# Display.net
KiCad netlist of a schematic drawn in Altium Designer
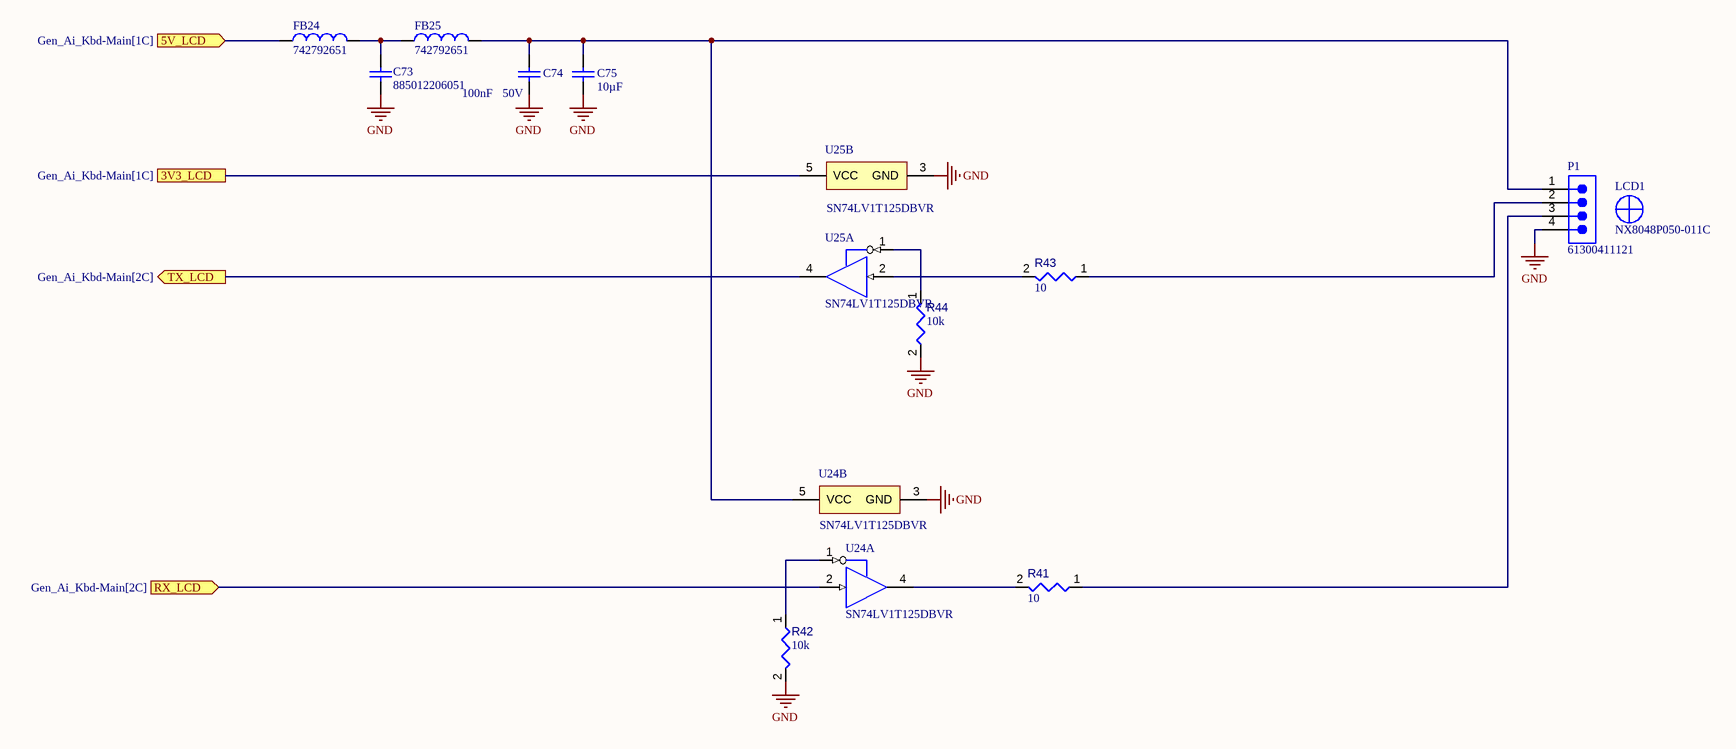
[diagram p0: Display.SchDoc]

(export (version "E")
  (design (tool "Eeschema 10.0.6"))
  (components
    (comp (ref "C73")
      (value "885012206051")
      (footprint "WCAP-CSGP_0603_L1.6W0.8H0.8_Reflow")
      (description "885012206051 Cap Cer 0.68UF 16V X7R 0603")
      (fields (field (name "TOLERANCE") "10%"))
      (libsource (lib "Altium Content Vault") (part "Capacitor_Non-Polarized"))
    )
    (comp (ref "C74")
      (value "885012206095")
      (footprint "WCAP-CSGP_0603_L1.6W0.8H0.8_Reflow")
      (description "WCAP-CSGP Multilayer Ceramic Chip Capacitor, General Purpose, size 0603, X7R, 100nF, 50VDC")
      (fields
        (field (name "CAPACITANCE") "100nF")
        (field (name "MANUFACTURER") "Wurth Elektronik")
        (field (name "RATED VOLTAGE (DC)") "50V")
      )
      (libsource (lib "Test365") (part "885012209047R"))
    )
    (comp (ref "C75")
      (value "885012106006")
      (footprint "WCAP-CSGP_0603_L1.6W0.8H0.8_Reflow")
      (description "WCAP-CSGP Multilayer Ceramic Chip Capacitor, General Purpose, size 0603, X5R, 10µF, 6.3VDC")
      (fields (field (name "MANUFACTURER") "Wurth Elektronik") (field (name "CAPACITANCE") "10µF"))
      (libsource (lib "Test365") (part "885012209047R"))
    )
    (comp (ref "FB24")
      (value "742792651")
      (footprint "WE-CBF_0603_L1.6W0.8H0.8_HC")
      (fields (field (name "TOLERANCE") "25%"))
      (libsource (lib "Altium Content Vault") (part "Ferrite"))
    )
    (comp (ref "FB25")
      (value "742792651")
      (footprint "WE-CBF_0603_L1.6W0.8H0.8_HC")
      (fields (field (name "TOLERANCE") "25%"))
      (libsource (lib "Altium Content Vault") (part "Ferrite"))
    )
    (comp (ref "LCD1")
      (value "NX8048P050-011C")
      (footprint "NEXTION 5.5Inch")
      (description "Nextion 5.5 Inch LCD")
      (libsource (lib "Test365") (part "NX8048P050-011C"))
    )
    (comp (ref "P1")
      (value "61300411121")
      (footprint "61300411121")
      (libsource (lib "Altium Content Vault") (part "Header_Male_1R_04P"))
    )
    (comp (ref "R41")
      (value "10")
      (footprint "RESC1608X55X25ML10T15")
      (description "Chip Resistor, 10 KOhm, +/- 1%, 01 W, -55 to 155 degC, 0603 (1608 Metric)")
      (fields (field (name "POWER") "100mW") (field (name "TOLERANCE") "1%"))
      (libsource (lib "Test365") (part "RES-2"))
    )
    (comp (ref "R42")
      (value "10k")
      (footprint "RESC1608X55X25ML10T15")
      (description "Chip Resistor, 10 KOhm, +/- 1%, 01 W, -55 to 155 degC, 0603 (1608 Metric)")
      (fields (field (name "POWER") "100mW") (field (name "TOLERANCE") "1%"))
      (libsource (lib "Test365") (part "RES-2"))
    )
    (comp (ref "R43")
      (value "10")
      (footprint "RESC1608X55X25ML10T15")
      (description "Chip Resistor, 10 KOhm, +/- 1%, 01 W, -55 to 155 degC, 0603 (1608 Metric)")
      (fields (field (name "POWER") "100mW") (field (name "TOLERANCE") "1%"))
      (libsource (lib "Test365") (part "RES-2"))
    )
    (comp (ref "R44")
      (value "10k")
      (footprint "RESC1608X55X25ML10T15")
      (description "Chip Resistor, 10 KOhm, +/- 1%, 01 W, -55 to 155 degC, 0603 (1608 Metric)")
      (fields (field (name "POWER") "100mW") (field (name "TOLERANCE") "1%"))
      (libsource (lib "Test365") (part "RES-2"))
    )
    (comp (ref "U24")
      (value "SN74LV1T125DBVR")
      (footprint "DBV0005A_M")
      (description "Single Power Supply, Single BUFFER GATE w/ 3-State Output (active low enable), DBV0005A, LARGE T&R")
      (fields
        (field (name "GENERIC PART NUMBER") "SN74LV1T125")
        (field (name "MANUFACTURER") "Texas Instruments")
      )
      (libsource (lib "Altium Content Vault") (part "TI-SN74AXXXX1X125-5"))
    )
    (comp (ref "U25")
      (value "SN74LV1T125DBVR")
      (footprint "DBV0005A_M")
      (description "Single Power Supply, Single BUFFER GATE w/ 3-State Output (active low enable), DBV0005A, LARGE T&R")
      (fields
        (field (name "GENERIC PART NUMBER") "SN74LV1T125")
        (field (name "MANUFACTURER") "Texas Instruments")
      )
      (libsource (lib "") (part "TI-SN74AXXXX1X125-5_1"))
    )
  )
  (nets
    (net (code "1") (name "/3V3_LCD") (class "Default")
      (node (ref "U25") (pin "5") (pinfunction "VCC_5") (pintype "power_in"))
    )
    (net (code "2") (name "/5V_LCD") (class "Default")
      (node (ref "FB24") (pin "1") (pinfunction "1_1") (pintype "passive"))
    )
    (net (code "3") (name "/RX_LCD") (class "Default")
      (node (ref "U24") (pin "2") (pinfunction "A_2") (pintype "input"))
    )
    (net (code "4") (name "/TX_LCD") (class "Default")
      (node (ref "U25") (pin "4") (pinfunction "Y_4") (pintype "tri_state"))
    )
    (net (code "5") (name "GND") (class "Default")
      (node (ref "C73") (pin "1") (pinfunction "1_1") (pintype "passive"))
      (node (ref "C74") (pin "1") (pinfunction "1_1") (pintype "passive"))
      (node (ref "C75") (pin "1") (pinfunction "1_1") (pintype "passive"))
      (node (ref "P1") (pin "4") (pinfunction "4_4") (pintype "passive"))
      (node (ref "R42") (pin "2") (pinfunction "2_2") (pintype "passive"))
      (node (ref "R44") (pin "2") (pinfunction "2_2") (pintype "passive"))
      (node (ref "U24") (pin "3") (pinfunction "GND_3") (pintype "power_in"))
      (node (ref "U25") (pin "3") (pinfunction "GND_3") (pintype "power_in"))
    )
    (net (code "6") (name "Net-(C73-Pad2)") (class "Default")
      (node (ref "C73") (pin "2") (pinfunction "2_2") (pintype "passive"))
      (node (ref "FB24") (pin "2") (pinfunction "2_2") (pintype "passive"))
      (node (ref "FB25") (pin "1") (pinfunction "1_1") (pintype "passive"))
    )
    (net (code "7") (name "Net-(P1-Pad2)") (class "Default")
      (node (ref "P1") (pin "2") (pinfunction "2_2") (pintype "passive"))
      (node (ref "R43") (pin "1") (pinfunction "1_1") (pintype "passive"))
    )
    (net (code "8") (name "Net-(P1-Pad3)") (class "Default")
      (node (ref "P1") (pin "3") (pinfunction "3_3") (pintype "passive"))
      (node (ref "R41") (pin "1") (pinfunction "1_1") (pintype "passive"))
    )
    (net (code "9") (name "Net-(U24A-Y)") (class "Default")
      (node (ref "R41") (pin "2") (pinfunction "2_2") (pintype "passive"))
      (node (ref "U24") (pin "4") (pinfunction "Y_4") (pintype "tri_state"))
    )
    (net (code "10") (name "Net-(U24A-~{OE})") (class "Default")
      (node (ref "R42") (pin "1") (pinfunction "1_1") (pintype "passive"))
      (node (ref "U24") (pin "1") (pinfunction "~{OE}_1") (pintype "input"))
    )
    (net (code "11") (name "Net-(U24B-VCC)") (class "Default")
      (node (ref "C74") (pin "2") (pinfunction "2_2") (pintype "passive"))
      (node (ref "C75") (pin "2") (pinfunction "2_2") (pintype "passive"))
      (node (ref "FB25") (pin "2") (pinfunction "2_2") (pintype "passive"))
      (node (ref "P1") (pin "1") (pinfunction "1_1") (pintype "passive"))
      (node (ref "U24") (pin "5") (pinfunction "VCC_5") (pintype "power_in"))
    )
    (net (code "12") (name "Net-(U25A-A)") (class "Default")
      (node (ref "R43") (pin "2") (pinfunction "2_2") (pintype "passive"))
      (node (ref "U25") (pin "2") (pinfunction "A_2") (pintype "input"))
    )
    (net (code "13") (name "Net-(U25A-~{OE})") (class "Default")
      (node (ref "R44") (pin "1") (pinfunction "1_1") (pintype "passive"))
      (node (ref "U25") (pin "1") (pinfunction "~{OE}_1") (pintype "input"))
    )
    (net (code "14") (name "unconnected-(LCD1-Pad1)") (class "Default")
      (node (ref "LCD1") (pin "1") (pinfunction "1_1") (pintype "passive"))
    )
  )
)
